# Sheet1.net
KiCad netlist of a schematic drawn in Altium Designer
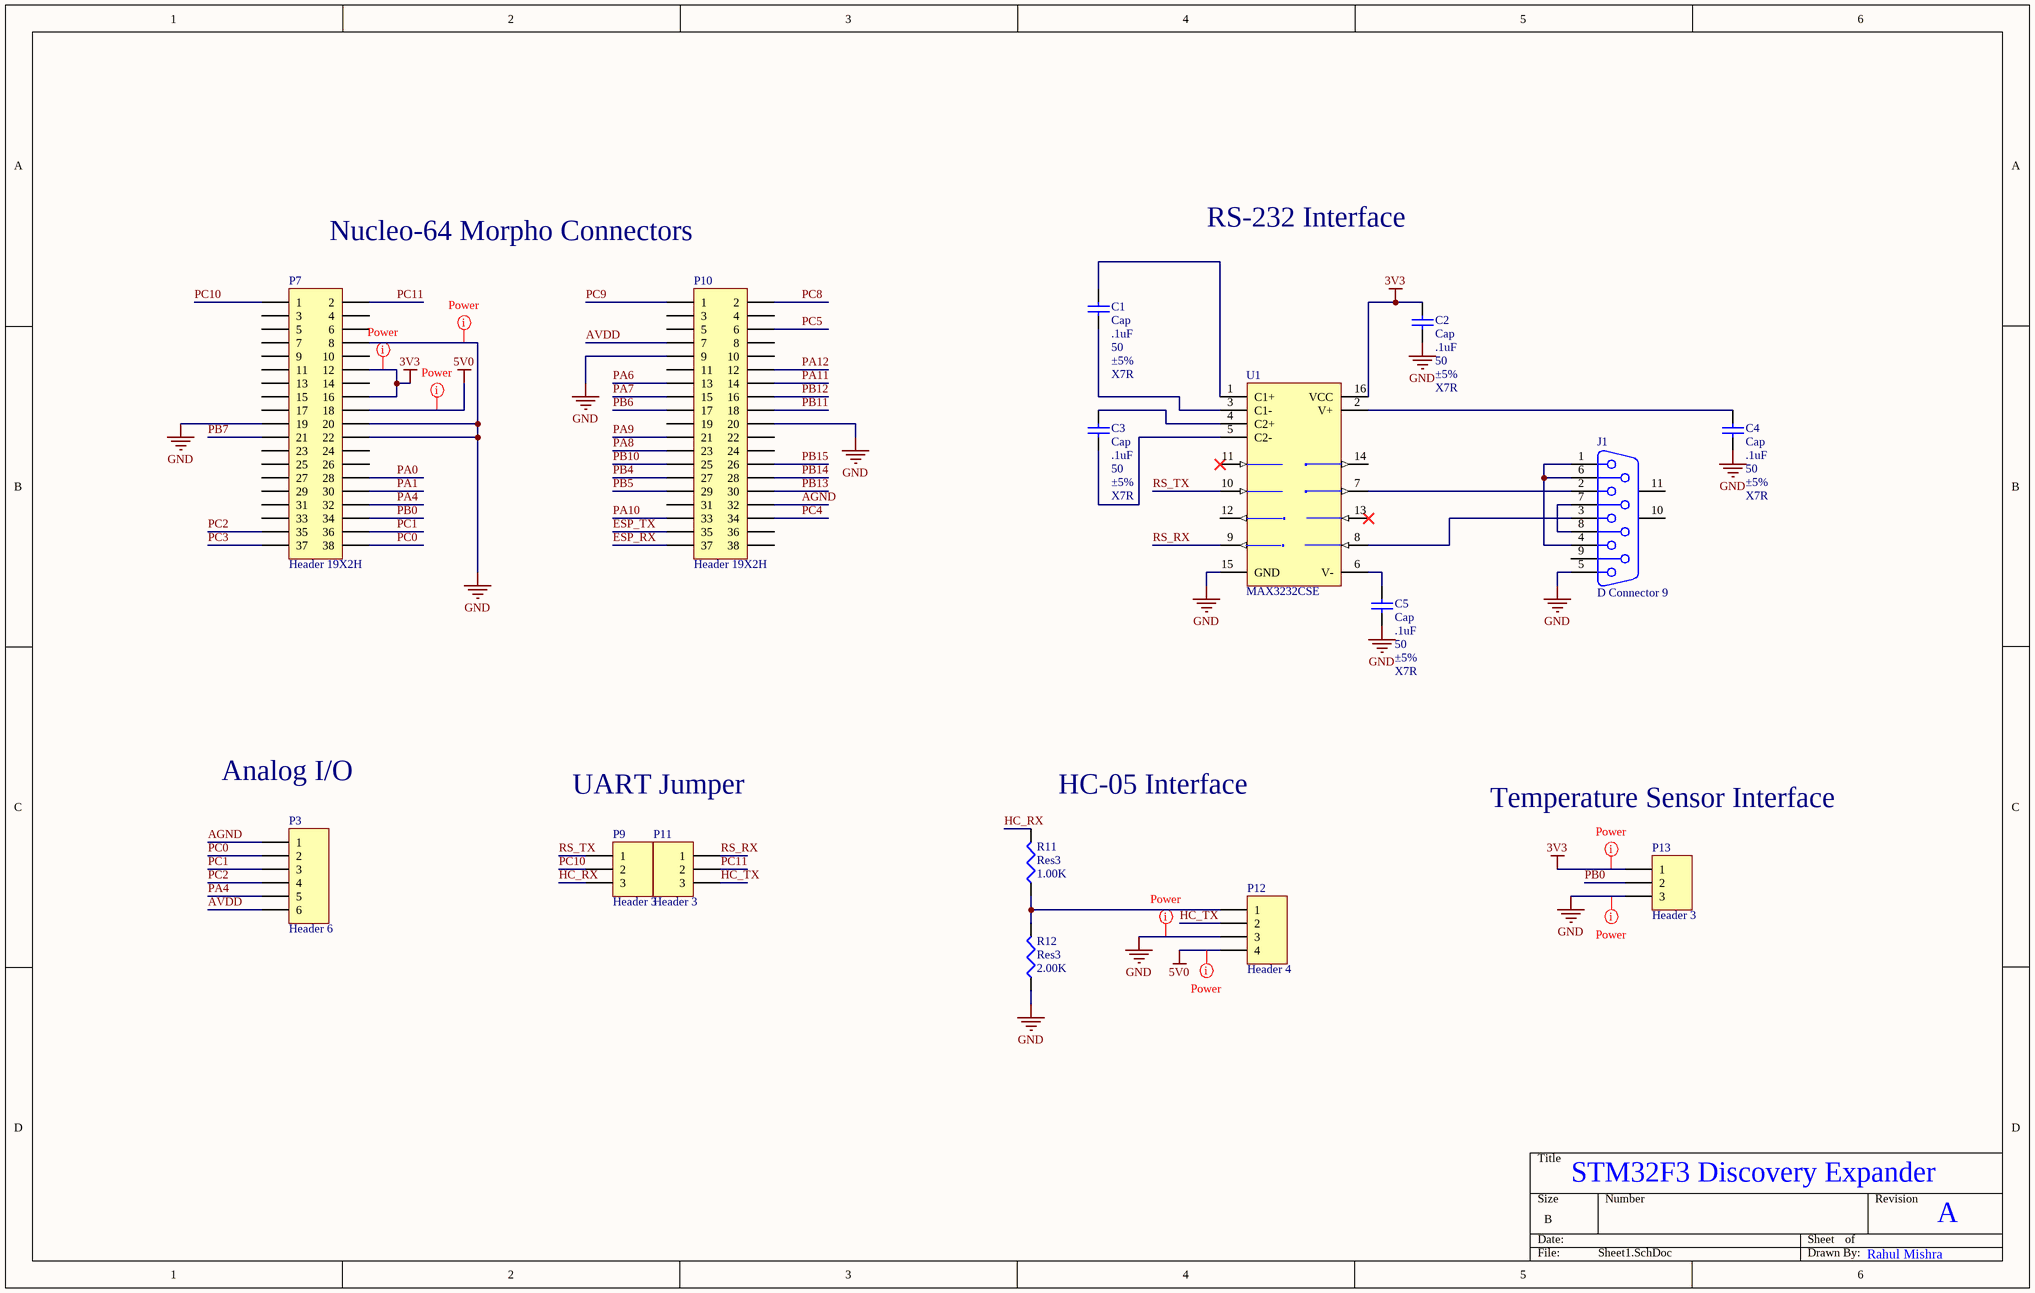
[diagram p0: Sheet1.SchDoc]

(export (version "E")
  (design (tool "Eeschema 10.0.6"))
  (components
    (comp (ref "C1")
      (value "Cap")
      (footprint "CAPC2012X09M")
      (description "CAP CER .1uF 50v X7R 0805")
      (fields
        (field (name "ALTIUM_VALUE") ".1uF")
        (field (name "WV") "50")
        (field (name "TOLERANCE") "±5%")
        (field (name "TYPE") "X7R")
        (field (name "MPN") "C0805C104J5RACTU")
      )
      (libsource (lib "esd_library") (part "CAP-X7R-.1uF-50V-±5%"))
    )
    (comp (ref "C2")
      (value "Cap")
      (footprint "CAPC2012X09M")
      (description "CAP CER .1uF 50v X7R 0805")
      (fields
        (field (name "ALTIUM_VALUE") ".1uF")
        (field (name "WV") "50")
        (field (name "TOLERANCE") "±5%")
        (field (name "TYPE") "X7R")
        (field (name "MPN") "C0805C104J5RACTU")
      )
      (libsource (lib "esd_library") (part "CAP-X7R-.1uF-50V-±5%"))
    )
    (comp (ref "C3")
      (value "Cap")
      (footprint "CAPC2012X09M")
      (description "CAP CER .1uF 50v X7R 0805")
      (fields
        (field (name "ALTIUM_VALUE") ".1uF")
        (field (name "WV") "50")
        (field (name "TOLERANCE") "±5%")
        (field (name "TYPE") "X7R")
        (field (name "MPN") "C0805C104J5RACTU")
      )
      (libsource (lib "esd_library") (part "CAP-X7R-.1uF-50V-±5%"))
    )
    (comp (ref "C4")
      (value "Cap")
      (footprint "CAPC2012X09M")
      (description "CAP CER .1uF 50v X7R 0805")
      (fields
        (field (name "ALTIUM_VALUE") ".1uF")
        (field (name "WV") "50")
        (field (name "TOLERANCE") "±5%")
        (field (name "TYPE") "X7R")
        (field (name "MPN") "C0805C104J5RACTU")
      )
      (libsource (lib "esd_library") (part "CAP-X7R-.1uF-50V-±5%"))
    )
    (comp (ref "C5")
      (value "Cap")
      (footprint "CAPC2012X09M")
      (description "CAP CER .1uF 50v X7R 0805")
      (fields
        (field (name "ALTIUM_VALUE") ".1uF")
        (field (name "WV") "50")
        (field (name "TOLERANCE") "±5%")
        (field (name "TYPE") "X7R")
        (field (name "MPN") "C0805C104J5RACTU")
      )
      (libsource (lib "esd_library") (part "CAP-X7R-.1uF-50V-±5%"))
    )
    (comp (ref "J1")
      (value "D Connector 9")
      (footprint "DSUB1.385-2H9")
      (description "Receptacle Assembly, 9 Position, Right Angle")
      (fields (field (name "MPN") "ADF09A-KG-TASB3-R"))
      (libsource (lib "esd_library") (part "D Connector 9"))
    )
    (comp (ref "P3")
      (value "Header 6")
      (footprint "HDR1X6")
      (description "Header, 6-Pin Male")
      (fields (field (name "MPN") "PEC06SFAN"))
      (libsource (lib "esd_library") (part "Header 6"))
    )
    (comp (ref "P7")
      (value "Header 19X2H")
      (footprint "PPPC192LFBN-RC")
      (description "38 Position Header Connector 0.100in (2.54mm) Through Hole Gold")
      (fields (field (name "MPN") "PPPC192LFBN-RC"))
      (libsource (lib "esd_library") (part "Header 19X2H"))
    )
    (comp (ref "P9")
      (value "Header 3")
      (footprint "HDR1X3")
      (description "Header, 3-Pin Male")
      (fields (field (name "MPN") "PEC03SFAN"))
      (libsource (lib "esd_library") (part "Header 3"))
    )
    (comp (ref "P10")
      (value "Header 19X2H")
      (footprint "PPPC192LFBN-RC")
      (description "38 Position Header Connector 0.100in (2.54mm) Through Hole Gold")
      (fields (field (name "MPN") "PPPC192LFBN-RC"))
      (libsource (lib "esd_library") (part "Header 19X2H"))
    )
    (comp (ref "P11")
      (value "Header 3")
      (footprint "HDR1X3")
      (description "Header, 3-Pin Male")
      (fields (field (name "MPN") "PEC03SFAN"))
      (libsource (lib "") (part "Header 3_1"))
    )
    (comp (ref "P12")
      (value "Header 4")
      (footprint "HDR1X4")
      (description "Header, 4-Pin Male")
      (fields (field (name "MPN") "PEC04SFAN"))
      (libsource (lib "esd_library") (part "Header 4"))
    )
    (comp (ref "P13")
      (value "Header 3")
      (footprint "HDR1X3")
      (description "Header, 3-Pin Male")
      (fields (field (name "MPN") "PEC03SFAN"))
      (libsource (lib "esd_library") (part "Header 3"))
    )
    (comp (ref "R11")
      (value "Res3")
      (footprint "RESC2112X05M")
      (description "RES SMD 1.00K OHM 1% 1/8W 0805")
      (fields (field (name "ALTIUM_VALUE") "1.00K") (field (name "MPN") "CRCW08051K00FKEA"))
      (libsource (lib "esd_library") (part "Resistor_1.00K"))
    )
    (comp (ref "R12")
      (value "Res3")
      (footprint "RESC2112X05M")
      (description "RES SMD 2.00K OHM 1% 1/8W 0805")
      (fields (field (name "ALTIUM_VALUE") "2.00K") (field (name "MPN") "CRCW08052K00FKEA"))
      (libsource (lib "esd_library") (part "Resistor_2.00K"))
    )
    (comp (ref "U1")
      (value "MAX3232CSE")
      (footprint "NSO16_N")
      (description "3.0V TO 5.5V, Low-Power, up to 1Mbps, True RS-232 Transceiver Using Four 0.1µF External Capacitor")
      (fields (field (name "MPN") "MAX3232CSE+") (field (name "PUBLISHER") "Altium Limited"))
      (libsource (lib "esd_library") (part "MAX3232CSE"))
    )
  )
  (nets
    (net (code "2") (name "/AGND") (class "Default")
      (node (ref "P10") (pin "32") (pinfunction "32_32") (pintype "passive"))
      (node (ref "P3") (pin "1") (pinfunction "1_1") (pintype "passive"))
    )
    (net (code "3") (name "/AVDD") (class "Default")
      (node (ref "P10") (pin "7") (pinfunction "7_7") (pintype "passive"))
      (node (ref "P3") (pin "6") (pinfunction "6_6") (pintype "passive"))
    )
    (net (code "4") (name "/ESP_RX") (class "Default")
      (node (ref "P10") (pin "37") (pinfunction "37_37") (pintype "passive"))
    )
    (net (code "5") (name "/ESP_TX") (class "Default")
      (node (ref "P10") (pin "35") (pinfunction "35_35") (pintype "passive"))
    )
    (net (code "6") (name "/HC_RX") (class "Default")
      (node (ref "P9") (pin "3") (pinfunction "3_3") (pintype "passive"))
      (node (ref "R11") (pin "2") (pinfunction "2_2") (pintype "passive"))
    )
    (net (code "7") (name "/HC_TX") (class "Default")
      (node (ref "P11") (pin "3") (pinfunction "3_3") (pintype "passive"))
      (node (ref "P12") (pin "2") (pinfunction "2_2") (pintype "passive"))
    )
    (net (code "8") (name "/PA0") (class "Default")
      (node (ref "P7") (pin "28") (pinfunction "28_28") (pintype "passive"))
    )
    (net (code "9") (name "/PA1") (class "Default")
      (node (ref "P7") (pin "30") (pinfunction "30_30") (pintype "passive"))
    )
    (net (code "10") (name "/PA4") (class "Default")
      (node (ref "P3") (pin "5") (pinfunction "5_5") (pintype "passive"))
      (node (ref "P7") (pin "32") (pinfunction "32_32") (pintype "passive"))
    )
    (net (code "11") (name "/PA6") (class "Default")
      (node (ref "P10") (pin "13") (pinfunction "13_13") (pintype "passive"))
    )
    (net (code "12") (name "/PA7") (class "Default")
      (node (ref "P10") (pin "15") (pinfunction "15_15") (pintype "passive"))
    )
    (net (code "13") (name "/PA8") (class "Default")
      (node (ref "P10") (pin "23") (pinfunction "23_23") (pintype "passive"))
    )
    (net (code "14") (name "/PA9") (class "Default")
      (node (ref "P10") (pin "21") (pinfunction "21_21") (pintype "passive"))
    )
    (net (code "15") (name "/PA10") (class "Default")
      (node (ref "P10") (pin "33") (pinfunction "33_33") (pintype "passive"))
    )
    (net (code "16") (name "/PA11") (class "Default")
      (node (ref "P10") (pin "14") (pinfunction "14_14") (pintype "passive"))
    )
    (net (code "17") (name "/PA12") (class "Default")
      (node (ref "P10") (pin "12") (pinfunction "12_12") (pintype "passive"))
    )
    (net (code "18") (name "/PB0") (class "Default")
      (node (ref "P13") (pin "2") (pinfunction "2_2") (pintype "passive"))
      (node (ref "P7") (pin "34") (pinfunction "34_34") (pintype "passive"))
    )
    (net (code "19") (name "/PB4") (class "Default")
      (node (ref "P10") (pin "27") (pinfunction "27_27") (pintype "passive"))
    )
    (net (code "20") (name "/PB5") (class "Default")
      (node (ref "P10") (pin "29") (pinfunction "29_29") (pintype "passive"))
    )
    (net (code "21") (name "/PB6") (class "Default")
      (node (ref "P10") (pin "17") (pinfunction "17_17") (pintype "passive"))
    )
    (net (code "22") (name "/PB7") (class "Default")
      (node (ref "P7") (pin "21") (pinfunction "21_21") (pintype "passive"))
    )
    (net (code "23") (name "/PB10") (class "Default")
      (node (ref "P10") (pin "25") (pinfunction "25_25") (pintype "passive"))
    )
    (net (code "24") (name "/PB11") (class "Default")
      (node (ref "P10") (pin "18") (pinfunction "18_18") (pintype "passive"))
    )
    (net (code "25") (name "/PB12") (class "Default")
      (node (ref "P10") (pin "16") (pinfunction "16_16") (pintype "passive"))
    )
    (net (code "26") (name "/PB13") (class "Default")
      (node (ref "P10") (pin "30") (pinfunction "30_30") (pintype "passive"))
    )
    (net (code "27") (name "/PB14") (class "Default")
      (node (ref "P10") (pin "28") (pinfunction "28_28") (pintype "passive"))
    )
    (net (code "28") (name "/PB15") (class "Default")
      (node (ref "P10") (pin "26") (pinfunction "26_26") (pintype "passive"))
    )
    (net (code "29") (name "/PC0") (class "Default")
      (node (ref "P3") (pin "2") (pinfunction "2_2") (pintype "passive"))
      (node (ref "P7") (pin "38") (pinfunction "38_38") (pintype "passive"))
    )
    (net (code "30") (name "/PC1") (class "Default")
      (node (ref "P3") (pin "3") (pinfunction "3_3") (pintype "passive"))
      (node (ref "P7") (pin "36") (pinfunction "36_36") (pintype "passive"))
    )
    (net (code "31") (name "/PC2") (class "Default")
      (node (ref "P3") (pin "4") (pinfunction "4_4") (pintype "passive"))
      (node (ref "P7") (pin "35") (pinfunction "35_35") (pintype "passive"))
    )
    (net (code "32") (name "/PC3") (class "Default")
      (node (ref "P7") (pin "37") (pinfunction "37_37") (pintype "passive"))
    )
    (net (code "33") (name "/PC4") (class "Default")
      (node (ref "P10") (pin "34") (pinfunction "34_34") (pintype "passive"))
    )
    (net (code "34") (name "/PC5") (class "Default")
      (node (ref "P10") (pin "6") (pinfunction "6_6") (pintype "passive"))
    )
    (net (code "35") (name "/PC8") (class "Default")
      (node (ref "P10") (pin "2") (pinfunction "2_2") (pintype "passive"))
    )
    (net (code "36") (name "/PC9") (class "Default")
      (node (ref "P10") (pin "1") (pinfunction "1_1") (pintype "passive"))
    )
    (net (code "37") (name "/PC10") (class "Default")
      (node (ref "P7") (pin "1") (pinfunction "1_1") (pintype "passive"))
      (node (ref "P9") (pin "2") (pinfunction "2_2") (pintype "passive"))
    )
    (net (code "38") (name "/PC11") (class "Default")
      (node (ref "P11") (pin "2") (pinfunction "2_2") (pintype "passive"))
      (node (ref "P7") (pin "2") (pinfunction "2_2") (pintype "passive"))
    )
    (net (code "39") (name "/RS_RX") (class "Default")
      (node (ref "P11") (pin "1") (pinfunction "1_1") (pintype "passive"))
      (node (ref "U1") (pin "9") (pinfunction "R2OUT_9") (pintype "output"))
    )
    (net (code "40") (name "/RS_TX") (class "Default")
      (node (ref "P9") (pin "1") (pinfunction "1_1") (pintype "passive"))
      (node (ref "U1") (pin "10") (pinfunction "T2IN_10") (pintype "input"))
    )
    (net (code "41") (name "3V3") (class "Default")
      (node (ref "C2") (pin "2") (pinfunction "2_2") (pintype "passive"))
      (node (ref "P13") (pin "1") (pinfunction "1_1") (pintype "passive"))
      (node (ref "P7") (pin "12") (pinfunction "12_12") (pintype "passive"))
      (node (ref "P7") (pin "16") (pinfunction "16_16") (pintype "passive"))
      (node (ref "U1") (pin "16") (pinfunction "VCC_16") (pintype "power_in"))
    )
    (net (code "42") (name "5V0") (class "Default")
      (node (ref "P12") (pin "4") (pinfunction "4_4") (pintype "passive"))
      (node (ref "P7") (pin "18") (pinfunction "18_18") (pintype "passive"))
    )
    (net (code "43") (name "GND") (class "Default")
      (node (ref "C2") (pin "1") (pinfunction "1_1") (pintype "passive"))
      (node (ref "C4") (pin "1") (pinfunction "1_1") (pintype "passive"))
      (node (ref "C5") (pin "1") (pinfunction "1_1") (pintype "passive"))
      (node (ref "J1") (pin "5") (pinfunction "5_5") (pintype "passive"))
      (node (ref "P10") (pin "20") (pinfunction "20_20") (pintype "passive"))
      (node (ref "P10") (pin "9") (pinfunction "9_9") (pintype "passive"))
      (node (ref "P12") (pin "3") (pinfunction "3_3") (pintype "passive"))
      (node (ref "P13") (pin "3") (pinfunction "3_3") (pintype "passive"))
      (node (ref "P7") (pin "19") (pinfunction "19_19") (pintype "passive"))
      (node (ref "P7") (pin "20") (pinfunction "20_20") (pintype "passive"))
      (node (ref "P7") (pin "22") (pinfunction "22_22") (pintype "passive"))
      (node (ref "P7") (pin "8") (pinfunction "8_8") (pintype "passive"))
      (node (ref "R12") (pin "1") (pinfunction "1_1") (pintype "passive"))
      (node (ref "U1") (pin "15") (pinfunction "GND_15") (pintype "power_in"))
    )
    (net (code "44") (name "Net-(J1-Pad1)") (class "Default")
      (node (ref "J1") (pin "1") (pinfunction "1_1") (pintype "passive"))
      (node (ref "J1") (pin "4") (pinfunction "4_4") (pintype "passive"))
      (node (ref "J1") (pin "6") (pinfunction "6_6") (pintype "passive"))
    )
    (net (code "45") (name "Net-(J1-Pad7)") (class "Default")
      (node (ref "J1") (pin "7") (pinfunction "7_7") (pintype "passive"))
      (node (ref "J1") (pin "8") (pinfunction "8_8") (pintype "passive"))
    )
    (net (code "46") (name "Net-(P12-Pad1)") (class "Default")
      (node (ref "P12") (pin "1") (pinfunction "1_1") (pintype "passive"))
      (node (ref "R11") (pin "1") (pinfunction "1_1") (pintype "passive"))
      (node (ref "R12") (pin "2") (pinfunction "2_2") (pintype "passive"))
    )
    (net (code "47") (name "Net-(U1-C1+)") (class "Default")
      (node (ref "C1") (pin "2") (pinfunction "2_2") (pintype "passive"))
      (node (ref "U1") (pin "1") (pinfunction "C1+_1") (pintype "passive"))
    )
    (net (code "48") (name "Net-(U1-C1-)") (class "Default")
      (node (ref "C1") (pin "1") (pinfunction "1_1") (pintype "passive"))
      (node (ref "U1") (pin "3") (pinfunction "C1-_3") (pintype "passive"))
    )
    (net (code "49") (name "Net-(U1-C2+)") (class "Default")
      (node (ref "C3") (pin "2") (pinfunction "2_2") (pintype "passive"))
      (node (ref "U1") (pin "4") (pinfunction "C2+_4") (pintype "passive"))
    )
    (net (code "50") (name "Net-(U1-C2-)") (class "Default")
      (node (ref "C3") (pin "1") (pinfunction "1_1") (pintype "passive"))
      (node (ref "U1") (pin "5") (pinfunction "C2-_5") (pintype "passive"))
    )
    (net (code "51") (name "Net-(U1-R2IN)") (class "Default")
      (node (ref "J1") (pin "3") (pinfunction "3_3") (pintype "passive"))
      (node (ref "U1") (pin "8") (pinfunction "R2IN_8") (pintype "input"))
    )
    (net (code "52") (name "Net-(U1-T2OUT)") (class "Default")
      (node (ref "J1") (pin "2") (pinfunction "2_2") (pintype "passive"))
      (node (ref "U1") (pin "7") (pinfunction "T2OUT_7") (pintype "output"))
    )
    (net (code "53") (name "Net-(U1-V+)") (class "Default")
      (node (ref "C4") (pin "2") (pinfunction "2_2") (pintype "passive"))
      (node (ref "U1") (pin "2") (pinfunction "V+_2") (pintype "power_in"))
    )
    (net (code "54") (name "Net-(U1-V-)") (class "Default")
      (node (ref "C5") (pin "2") (pinfunction "2_2") (pintype "passive"))
      (node (ref "U1") (pin "6") (pinfunction "V-_6") (pintype "power_in"))
    )
    (net (code "55") (name "unconnected-(J1-MH1-Pad10)") (class "Default")
      (node (ref "J1") (pin "10") (pinfunction "MH1_10") (pintype "passive"))
    )
    (net (code "56") (name "unconnected-(J1-MH2-Pad11)") (class "Default")
      (node (ref "J1") (pin "11") (pinfunction "MH2_11") (pintype "passive"))
    )
    (net (code "57") (name "unconnected-(J1-Pad9)") (class "Default")
      (node (ref "J1") (pin "9") (pinfunction "9_9") (pintype "passive"))
    )
    (net (code "58") (name "unconnected-(P7-Pad3)") (class "Default")
      (node (ref "P7") (pin "3") (pinfunction "3_3") (pintype "passive"))
    )
    (net (code "59") (name "unconnected-(P7-Pad4)") (class "Default")
      (node (ref "P7") (pin "4") (pinfunction "4_4") (pintype "passive"))
    )
    (net (code "60") (name "unconnected-(P7-Pad5)") (class "Default")
      (node (ref "P7") (pin "5") (pinfunction "5_5") (pintype "passive"))
    )
    (net (code "61") (name "unconnected-(P7-Pad6)") (class "Default")
      (node (ref "P7") (pin "6") (pinfunction "6_6") (pintype "passive"))
    )
    (net (code "62") (name "unconnected-(P7-Pad7)") (class "Default")
      (node (ref "P7") (pin "7") (pinfunction "7_7") (pintype "passive"))
    )
    (net (code "63") (name "unconnected-(P7-Pad9)") (class "Default")
      (node (ref "P7") (pin "9") (pinfunction "9_9") (pintype "passive"))
    )
    (net (code "64") (name "unconnected-(P7-Pad10)") (class "Default")
      (node (ref "P7") (pin "10") (pinfunction "10_10") (pintype "passive"))
    )
    (net (code "65") (name "unconnected-(P7-Pad11)") (class "Default")
      (node (ref "P7") (pin "11") (pinfunction "11_11") (pintype "passive"))
    )
    (net (code "66") (name "unconnected-(P7-Pad13)") (class "Default")
      (node (ref "P7") (pin "13") (pinfunction "13_13") (pintype "passive"))
    )
    (net (code "67") (name "unconnected-(P7-Pad14)") (class "Default")
      (node (ref "P7") (pin "14") (pinfunction "14_14") (pintype "passive"))
    )
    (net (code "68") (name "unconnected-(P7-Pad15)") (class "Default")
      (node (ref "P7") (pin "15") (pinfunction "15_15") (pintype "passive"))
    )
    (net (code "69") (name "unconnected-(P7-Pad17)") (class "Default")
      (node (ref "P7") (pin "17") (pinfunction "17_17") (pintype "passive"))
    )
    (net (code "70") (name "unconnected-(P7-Pad23)") (class "Default")
      (node (ref "P7") (pin "23") (pinfunction "23_23") (pintype "passive"))
    )
    (net (code "71") (name "unconnected-(P7-Pad24)") (class "Default")
      (node (ref "P7") (pin "24") (pinfunction "24_24") (pintype "passive"))
    )
    (net (code "72") (name "unconnected-(P7-Pad25)") (class "Default")
      (node (ref "P7") (pin "25") (pinfunction "25_25") (pintype "passive"))
    )
    (net (code "73") (name "unconnected-(P7-Pad26)") (class "Default")
      (node (ref "P7") (pin "26") (pinfunction "26_26") (pintype "passive"))
    )
    (net (code "74") (name "unconnected-(P7-Pad27)") (class "Default")
      (node (ref "P7") (pin "27") (pinfunction "27_27") (pintype "passive"))
    )
    (net (code "75") (name "unconnected-(P7-Pad29)") (class "Default")
      (node (ref "P7") (pin "29") (pinfunction "29_29") (pintype "passive"))
    )
    (net (code "76") (name "unconnected-(P7-Pad31)") (class "Default")
      (node (ref "P7") (pin "31") (pinfunction "31_31") (pintype "passive"))
    )
    (net (code "77") (name "unconnected-(P7-Pad33)") (class "Default")
      (node (ref "P7") (pin "33") (pinfunction "33_33") (pintype "passive"))
    )
    (net (code "78") (name "unconnected-(P10-Pad3)") (class "Default")
      (node (ref "P10") (pin "3") (pinfunction "3_3") (pintype "passive"))
    )
    (net (code "79") (name "unconnected-(P10-Pad4)") (class "Default")
      (node (ref "P10") (pin "4") (pinfunction "4_4") (pintype "passive"))
    )
    (net (code "80") (name "unconnected-(P10-Pad5)") (class "Default")
      (node (ref "P10") (pin "5") (pinfunction "5_5") (pintype "passive"))
    )
    (net (code "81") (name "unconnected-(P10-Pad8)") (class "Default")
      (node (ref "P10") (pin "8") (pinfunction "8_8") (pintype "passive"))
    )
    (net (code "82") (name "unconnected-(P10-Pad10)") (class "Default")
      (node (ref "P10") (pin "10") (pinfunction "10_10") (pintype "passive"))
    )
    (net (code "83") (name "unconnected-(P10-Pad11)") (class "Default")
      (node (ref "P10") (pin "11") (pinfunction "11_11") (pintype "passive"))
    )
    (net (code "84") (name "unconnected-(P10-Pad19)") (class "Default")
      (node (ref "P10") (pin "19") (pinfunction "19_19") (pintype "passive"))
    )
    (net (code "85") (name "unconnected-(P10-Pad22)") (class "Default")
      (node (ref "P10") (pin "22") (pinfunction "22_22") (pintype "passive"))
    )
    (net (code "86") (name "unconnected-(P10-Pad24)") (class "Default")
      (node (ref "P10") (pin "24") (pinfunction "24_24") (pintype "passive"))
    )
    (net (code "87") (name "unconnected-(P10-Pad31)") (class "Default")
      (node (ref "P10") (pin "31") (pinfunction "31_31") (pintype "passive"))
    )
    (net (code "88") (name "unconnected-(P10-Pad36)") (class "Default")
      (node (ref "P10") (pin "36") (pinfunction "36_36") (pintype "passive"))
    )
    (net (code "89") (name "unconnected-(P10-Pad38)") (class "Default")
      (node (ref "P10") (pin "38") (pinfunction "38_38") (pintype "passive"))
    )
    (net (code "90") (name "unconnected-(U1-R1IN-Pad13)") (class "Default")
      (node (ref "U1") (pin "13") (pinfunction "R1IN_13") (pintype "input+no_connect"))
    )
    (net (code "91") (name "unconnected-(U1-R1OUT-Pad12)") (class "Default")
      (node (ref "U1") (pin "12") (pinfunction "R1OUT_12") (pintype "output"))
    )
    (net (code "92") (name "unconnected-(U1-T1IN-Pad11)") (class "Default")
      (node (ref "U1") (pin "11") (pinfunction "T1IN_11") (pintype "input+no_connect"))
    )
    (net (code "93") (name "unconnected-(U1-T1OUT-Pad14)") (class "Default")
      (node (ref "U1") (pin "14") (pinfunction "T1OUT_14") (pintype "output"))
    )
  )
)
